# altium_hier_flash.net
KiCad netlist of a schematic drawn in Altium Designer
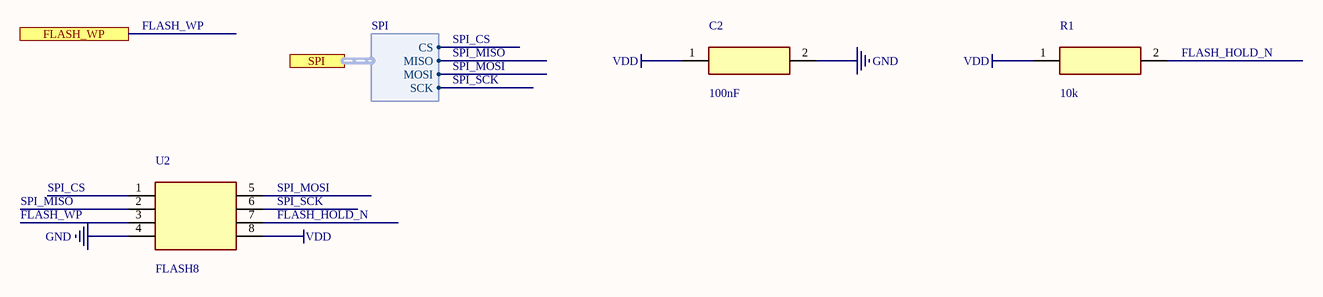
[diagram p0: altium_hier_flash.SchDoc]

(export (version "E")
  (design (tool "Eeschema 10.0.6"))
  (components
    (comp (ref "C2")
      (value "100nF")
      (footprint "FenoliteHier:C0603")
      (libsource (lib "FenoliteHier") (part "CAP"))
    )
    (comp (ref "R1")
      (value "10k")
      (footprint "FenoliteHier:R0603")
      (libsource (lib "FenoliteHier") (part "RES"))
    )
    (comp (ref "U2")
      (value "FLASH8")
      (footprint "FenoliteHier:SOIC8")
      (libsource (lib "FenoliteHier") (part "FLASH8"))
    )
  )
  (nets
    (net (code "2") (name "/FLASH_HOLD_N") (class "Default")
      (node (ref "R1") (pin "2") (pinfunction "2_2") (pintype "passive"))
      (node (ref "U2") (pin "7") (pinfunction "7_7") (pintype "passive"))
    )
    (net (code "3") (name "/FLASH_WP") (class "Default")
      (node (ref "U2") (pin "3") (pinfunction "3_3") (pintype "passive"))
    )
    (net (code "4") (name "/SPI_CS") (class "Default")
      (node (ref "U2") (pin "1") (pinfunction "1_1") (pintype "passive"))
    )
    (net (code "5") (name "/SPI_MISO") (class "Default")
      (node (ref "U2") (pin "2") (pinfunction "2_2") (pintype "passive"))
    )
    (net (code "6") (name "/SPI_MOSI") (class "Default")
      (node (ref "U2") (pin "5") (pinfunction "5_5") (pintype "passive"))
    )
    (net (code "7") (name "/SPI_SCK") (class "Default")
      (node (ref "U2") (pin "6") (pinfunction "6_6") (pintype "passive"))
    )
    (net (code "9") (name "GND") (class "Default")
      (node (ref "C2") (pin "2") (pinfunction "2_2") (pintype "passive"))
      (node (ref "U2") (pin "4") (pinfunction "4_4") (pintype "passive"))
    )
    (net (code "10") (name "VDD") (class "Default")
      (node (ref "C2") (pin "1") (pinfunction "1_1") (pintype "passive"))
      (node (ref "R1") (pin "1") (pinfunction "1_1") (pintype "passive"))
      (node (ref "U2") (pin "8") (pinfunction "8_8") (pintype "passive"))
    )
  )
)
